# Atom_S3_Module_-_Rev_C.net
KiCad netlist of a schematic drawn in EAGLE
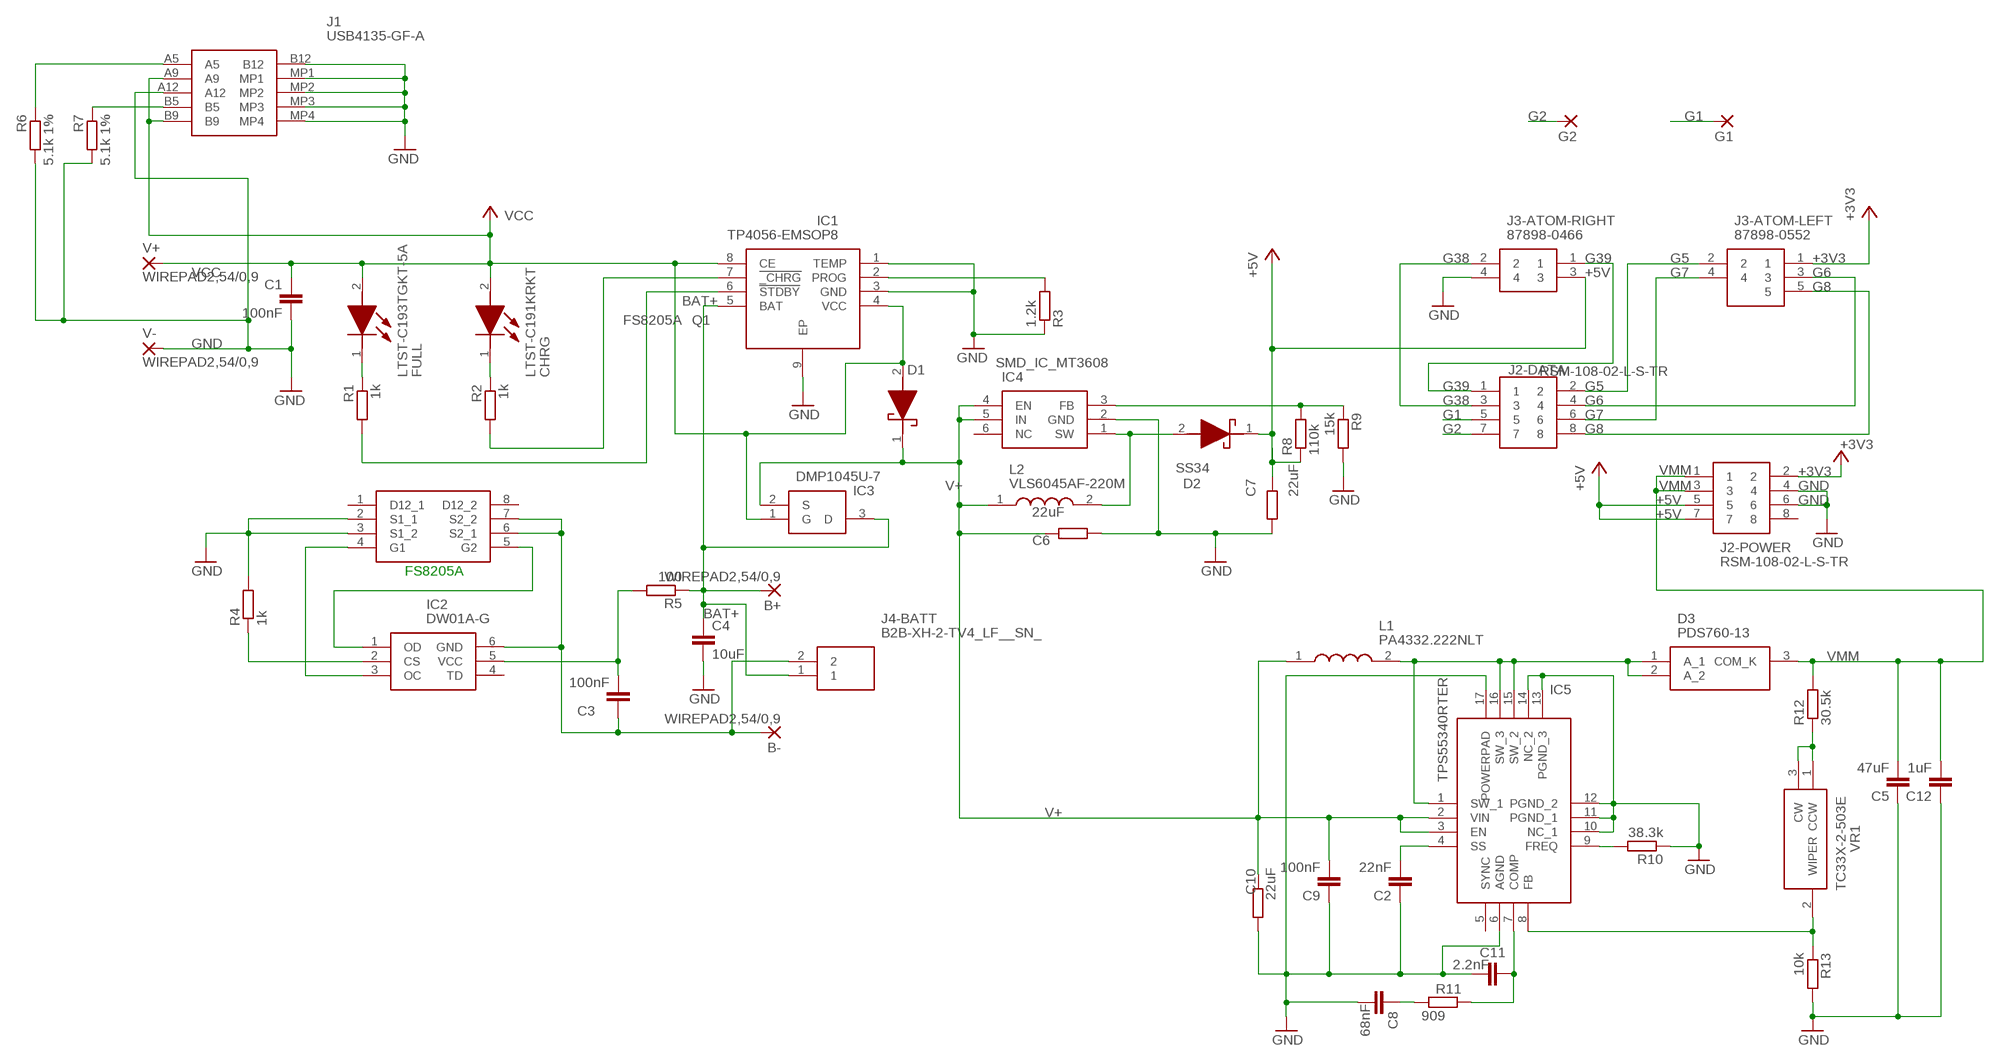
[diagram p0: schematic, sheet 1]

(export (version "E")
  (design (tool "Eeschema 10.0.6"))
  (components
    (comp (ref "B+")
      (value "WIREPAD2,54/0,9")
      (footprint "eagle-import:2,54_0,9")
      (libsource (lib "eagle-import") (part "WIREPAD2,54/0,9"))
    )
    (comp (ref "B-")
      (value "WIREPAD2,54/0,9")
      (footprint "eagle-import:2,54_0,9")
      (libsource (lib "eagle-import") (part "WIREPAD2,54/0,9"))
    )
    (comp (ref "C1")
      (value "100nF")
      (footprint "eagle-import:C0603")
      (libsource (lib "eagle-import") (part "C-EUC0603"))
    )
    (comp (ref "C2")
      (value "22nF")
      (footprint "eagle-import:C0603")
      (libsource (lib "eagle-import") (part "C-EUC0603"))
    )
    (comp (ref "C3")
      (value "100nF")
      (footprint "eagle-import:C0603")
      (libsource (lib "eagle-import") (part "C-EUC0603"))
    )
    (comp (ref "C4")
      (value "10uF")
      (footprint "eagle-import:C0603")
      (libsource (lib "eagle-import") (part "C-EUC0603"))
    )
    (comp (ref "C5")
      (value "47uF")
      (footprint "eagle-import:C1210")
      (libsource (lib "eagle-import") (part "C-EUC1210"))
    )
    (comp (ref "C6")
      (value "22uF")
      (footprint "eagle-import:R0805")
      (libsource (lib "eagle-import") (part "R-EU_R0805"))
    )
    (comp (ref "C7")
      (value "22uF")
      (footprint "eagle-import:R0805")
      (libsource (lib "eagle-import") (part "R-EU_R0805"))
    )
    (comp (ref "C8")
      (value "68nF")
      (footprint "eagle-import:C0603")
      (libsource (lib "eagle-import") (part "C-EUC0603"))
    )
    (comp (ref "C9")
      (value "100nF")
      (footprint "eagle-import:C0603")
      (libsource (lib "eagle-import") (part "C-EUC0603"))
    )
    (comp (ref "C10")
      (value "22uF")
      (footprint "eagle-import:R0805")
      (libsource (lib "eagle-import") (part "R-EU_R0805"))
    )
    (comp (ref "C11")
      (value "2.2nF")
      (footprint "eagle-import:C0603")
      (libsource (lib "eagle-import") (part "C-EUC0603"))
    )
    (comp (ref "C12")
      (value "1uF")
      (footprint "eagle-import:C0603")
      (libsource (lib "eagle-import") (part "C-EUC0603"))
    )
    (comp (ref "CHRG")
      (value "LTST-C191KRKT")
      (footprint "eagle-import:LEDC1608X55N")
      (fields (field (name "MOUSER_PART_NUMBER") "859-LTST-C191KRKT"))
      (libsource (lib "eagle-import") (part "LTST-C191KRKT"))
    )
    (comp (ref "D1")
      (value "SS34")
      (footprint "eagle-import:DIOM8059X256N")
      (fields (field (name "MOUSER_PART_NUMBER") "512-SS34"))
      (libsource (lib "eagle-import") (part "SS34"))
    )
    (comp (ref "D2")
      (value "SS34")
      (footprint "eagle-import:DIOM8059X256N")
      (fields (field (name "MOUSER_PART_NUMBER") "512-SS34"))
      (libsource (lib "eagle-import") (part "SS34"))
    )
    (comp (ref "D3")
      (value "PDS760-13")
      (footprint "eagle-import:PDS76013")
      (fields (field (name "MOUSER_PART_NUMBER") "621-PDS760-F"))
      (libsource (lib "eagle-import") (part "PDS760-13"))
    )
    (comp (ref "FULL")
      (value "LTST-C193TGKT-5A")
      (footprint "eagle-import:LEDC1608X45N")
      (fields (field (name "MOUSER_PART_NUMBER") "859-LTSTC193TGKT5A"))
      (libsource (lib "eagle-import") (part "LTST-C193TGKT-5A"))
    )
    (comp (ref "G1")
      (value "WIREPAD1,6/0,9")
      (footprint "eagle-import:1,6_0,9")
      (libsource (lib "eagle-import") (part "WIREPAD1,6/0,9"))
    )
    (comp (ref "G2")
      (value "WIREPAD1,6/0,9")
      (footprint "eagle-import:1,6_0,9")
      (libsource (lib "eagle-import") (part "WIREPAD1,6/0,9"))
    )
    (comp (ref "IC1")
      (value "TP4056-EMSOP8")
      (footprint "eagle-import:SOP65P490X110-9N")
      (libsource (lib "eagle-import") (part "TP4056-EMSOP8"))
    )
    (comp (ref "IC2")
      (value "DW01A-G")
      (footprint "eagle-import:SOT95P190X145-6N")
      (libsource (lib "eagle-import") (part "DW01A-G"))
    )
    (comp (ref "IC3")
      (value "DMP1045U-7")
      (footprint "eagle-import:SOT96P240X110-3N")
      (fields (field (name "MOUSER_PART_NUMBER") "621-DMP1045U-7"))
      (libsource (lib "eagle-import") (part "DMP1045U-7"))
    )
    (comp (ref "IC4")
      (value "SMD_IC_MT3608")
      (footprint "eagle-import:SOT95P280X145-6N")
      (fields
        (field (name "MANUFACTURER_PART_NUMBER") "SMD IC MT3608")
        (field (name "MOUSER_PART_NUMBER") "909-SMDICMT3608")
      )
      (libsource (lib "eagle-import") (part "SMD_IC_MT3608"))
    )
    (comp (ref "IC5")
      (value "TPS55340RTER")
      (footprint "eagle-import:QFN50P300X300X80-17N")
      (fields (field (name "MOUSER_PART_NUMBER") "595-TPS55340RTER"))
      (libsource (lib "eagle-import") (part "TPS55340RTER"))
    )
    (comp (ref "J1")
      (value "USB4135-GF-A")
      (footprint "eagle-import:USB4135GFA")
      (fields (field (name "MOUSER_PART_NUMBER") "640-USB4135-GF-A"))
      (libsource (lib "eagle-import") (part "USB4135-GF-A"))
    )
    (comp (ref "J2-DATA")
      (value "RSM-108-02-L-S-TR")
      (footprint "eagle-import:RSM10802LSTR")
      (fields (field (name "MOUSER_PART_NUMBER") "200-RSM10802LSTR"))
      (libsource (lib "eagle-import") (part "RSM-108-02-L-S-TR"))
    )
    (comp (ref "J2-POWER")
      (value "RSM-108-02-L-S-TR")
      (footprint "eagle-import:RSM10802LSTR")
      (fields (field (name "MOUSER_PART_NUMBER") "200-RSM10802LSTR"))
      (libsource (lib "eagle-import") (part "RSM-108-02-L-S-TR"))
    )
    (comp (ref "J3-ATOM-LEFT")
      (value "87898-0552")
      (footprint "eagle-import:878980552")
      (libsource (lib "eagle-import") (part "87898-0552"))
    )
    (comp (ref "J3-ATOM-RIGHT")
      (value "87898-0466")
      (footprint "eagle-import:878980466")
      (fields (field (name "MOUSER_PART_NUMBER") "538-87898-0466"))
      (libsource (lib "eagle-import") (part "87898-0466"))
    )
    (comp (ref "J4-BATT")
      (value "B2B-XH-2-TV4_LF__SN_")
      (footprint "eagle-import:B2BXH2TV4LFSN")
      (fields
        (field (name "MANUFACTURER_PART_NUMBER") "B2B-XH-2-TV4(LF)(SN)")
        (field (name "MOUSER_PART_NUMBER") "306-B2BXH2TV4LFSN")
      )
      (libsource (lib "eagle-import") (part "B2B-XH-2-TV4_LF__SN_"))
    )
    (comp (ref "L1")
      (value "PA4332.222NLT")
      (footprint "eagle-import:INDPM4042X200N")
      (fields (field (name "MOUSER_PART_NUMBER") "673-PA4332222NLT"))
      (libsource (lib "eagle-import") (part "PA4332.222NLT"))
    )
    (comp (ref "L2")
      (value "VLS6045AF-220M")
      (footprint "eagle-import:VLS6045")
      (fields (field (name "MOUSER_PART_NUMBER") "810-VLS6045AF-220M"))
      (libsource (lib "eagle-import") (part "VLS6045AF-220M"))
    )
    (comp (ref "Q1")
      (value "FS8205A")
      (footprint "eagle-import:SOP65P640X120-8N")
      (libsource (lib "eagle-import") (part "FS8205A"))
    )
    (comp (ref "R1")
      (value "1k")
      (footprint "eagle-import:R0603")
      (libsource (lib "eagle-import") (part "R-EU_R0603"))
    )
    (comp (ref "R2")
      (value "1k")
      (footprint "eagle-import:R0603")
      (libsource (lib "eagle-import") (part "R-EU_R0603"))
    )
    (comp (ref "R3")
      (value "1.2k")
      (footprint "eagle-import:R0603")
      (libsource (lib "eagle-import") (part "R-EU_R0603"))
    )
    (comp (ref "R4")
      (value "1k")
      (footprint "eagle-import:R0603")
      (libsource (lib "eagle-import") (part "R-EU_R0603"))
    )
    (comp (ref "R5")
      (value "100")
      (footprint "eagle-import:R0603")
      (libsource (lib "eagle-import") (part "R-EU_R0603"))
    )
    (comp (ref "R6")
      (value "5.1k 1%")
      (footprint "eagle-import:R0603")
      (libsource (lib "eagle-import") (part "R-EU_R0603"))
    )
    (comp (ref "R7")
      (value "5.1k 1%")
      (footprint "eagle-import:R0603")
      (libsource (lib "eagle-import") (part "R-EU_R0603"))
    )
    (comp (ref "R8")
      (value "110k")
      (footprint "eagle-import:R0603")
      (libsource (lib "eagle-import") (part "R-EU_R0603"))
    )
    (comp (ref "R9")
      (value "15k")
      (footprint "eagle-import:R0603")
      (libsource (lib "eagle-import") (part "R-EU_R0603"))
    )
    (comp (ref "R10")
      (value "38.3k")
      (footprint "eagle-import:R0603")
      (libsource (lib "eagle-import") (part "R-EU_R0603"))
    )
    (comp (ref "R11")
      (value "909")
      (footprint "eagle-import:R0603")
      (libsource (lib "eagle-import") (part "R-EU_R0603"))
    )
    (comp (ref "R12")
      (value "30.5k")
      (footprint "eagle-import:R0805")
      (libsource (lib "eagle-import") (part "R-EU_R0805"))
    )
    (comp (ref "R13")
      (value "10k")
      (footprint "eagle-import:R0603")
      (libsource (lib "eagle-import") (part "R-EU_R0603"))
    )
    (comp (ref "V+")
      (value "WIREPAD2,54/0,9")
      (footprint "eagle-import:2,54_0,9")
      (libsource (lib "eagle-import") (part "WIREPAD2,54/0,9"))
    )
    (comp (ref "V-")
      (value "WIREPAD2,54/0,9")
      (footprint "eagle-import:2,54_0,9")
      (libsource (lib "eagle-import") (part "WIREPAD2,54/0,9"))
    )
    (comp (ref "VR1")
      (value "TC33X-2-503E")
      (footprint "eagle-import:TC33X2503E")
      (fields (field (name "MOUSER_PART_NUMBER") "652-TC33X-2-503E"))
      (libsource (lib "eagle-import") (part "TC33X-2-503E"))
    )
  )
  (nets
    (net (code "1") (name "+3V3") (class "Default")
      (node (ref "J2-POWER") (pin "2") (pinfunction "2_2") (pintype "bidirectional"))
      (node (ref "J3-ATOM-LEFT") (pin "1") (pinfunction "1_1") (pintype "bidirectional"))
    )
    (net (code "2") (name "+5V") (class "Default")
      (node (ref "C7") (pin "2") (pinfunction "2_2") (pintype "passive"))
      (node (ref "D2") (pin "1") (pinfunction "K_1") (pintype "bidirectional"))
      (node (ref "J2-POWER") (pin "5") (pinfunction "5_5") (pintype "bidirectional"))
      (node (ref "J2-POWER") (pin "7") (pinfunction "7_7") (pintype "bidirectional"))
      (node (ref "J3-ATOM-RIGHT") (pin "3") (pinfunction "3_3") (pintype "bidirectional"))
      (node (ref "R8") (pin "1") (pinfunction "1_1") (pintype "passive"))
    )
    (net (code "3") (name "BAT+") (class "Default")
      (node (ref "B+") (pin "1") (pinfunction "P_1") (pintype "passive"))
      (node (ref "C4") (pin "1") (pinfunction "1_1") (pintype "passive"))
      (node (ref "IC1") (pin "5") (pinfunction "BAT_5") (pintype "bidirectional"))
      (node (ref "IC3") (pin "3") (pinfunction "D_3") (pintype "bidirectional"))
      (node (ref "J4-BATT") (pin "1") (pinfunction "1_1") (pintype "bidirectional"))
      (node (ref "R5") (pin "1") (pinfunction "1_1") (pintype "passive"))
    )
    (net (code "4") (name "G1") (class "Default")
      (node (ref "G1") (pin "1") (pinfunction "P_1") (pintype "passive"))
      (node (ref "J2-DATA") (pin "5") (pinfunction "5_5") (pintype "bidirectional"))
    )
    (net (code "5") (name "G2") (class "Default")
      (node (ref "G2") (pin "1") (pinfunction "P_1") (pintype "passive"))
      (node (ref "J2-DATA") (pin "7") (pinfunction "7_7") (pintype "bidirectional"))
    )
    (net (code "6") (name "G5") (class "Default")
      (node (ref "J2-DATA") (pin "2") (pinfunction "2_2") (pintype "bidirectional"))
      (node (ref "J3-ATOM-LEFT") (pin "2") (pinfunction "2_2") (pintype "bidirectional"))
    )
    (net (code "7") (name "G6") (class "Default")
      (node (ref "J2-DATA") (pin "4") (pinfunction "4_4") (pintype "bidirectional"))
      (node (ref "J3-ATOM-LEFT") (pin "3") (pinfunction "3_3") (pintype "bidirectional"))
    )
    (net (code "8") (name "G7") (class "Default")
      (node (ref "J2-DATA") (pin "6") (pinfunction "6_6") (pintype "bidirectional"))
      (node (ref "J3-ATOM-LEFT") (pin "4") (pinfunction "4_4") (pintype "bidirectional"))
    )
    (net (code "9") (name "G8") (class "Default")
      (node (ref "J2-DATA") (pin "8") (pinfunction "8_8") (pintype "bidirectional"))
      (node (ref "J3-ATOM-LEFT") (pin "5") (pinfunction "5_5") (pintype "bidirectional"))
    )
    (net (code "10") (name "G38") (class "Default")
      (node (ref "J2-DATA") (pin "3") (pinfunction "3_3") (pintype "bidirectional"))
      (node (ref "J3-ATOM-RIGHT") (pin "2") (pinfunction "2_2") (pintype "bidirectional"))
    )
    (net (code "11") (name "G39") (class "Default")
      (node (ref "J2-DATA") (pin "1") (pinfunction "1_1") (pintype "bidirectional"))
      (node (ref "J3-ATOM-RIGHT") (pin "1") (pinfunction "1_1") (pintype "bidirectional"))
    )
    (net (code "12") (name "GND") (class "Default")
      (node (ref "C1") (pin "2") (pinfunction "2_2") (pintype "passive"))
      (node (ref "C10") (pin "1") (pinfunction "1_1") (pintype "passive"))
      (node (ref "C11") (pin "2") (pinfunction "2_2") (pintype "passive"))
      (node (ref "C12") (pin "1") (pinfunction "1_1") (pintype "passive"))
      (node (ref "C2") (pin "1") (pinfunction "1_1") (pintype "passive"))
      (node (ref "C4") (pin "2") (pinfunction "2_2") (pintype "passive"))
      (node (ref "C5") (pin "1") (pinfunction "1_1") (pintype "passive"))
      (node (ref "C6") (pin "1") (pinfunction "1_1") (pintype "passive"))
      (node (ref "C7") (pin "1") (pinfunction "1_1") (pintype "passive"))
      (node (ref "C8") (pin "2") (pinfunction "2_2") (pintype "passive"))
      (node (ref "C9") (pin "1") (pinfunction "1_1") (pintype "passive"))
      (node (ref "IC1") (pin "1") (pinfunction "TEMP_1") (pintype "bidirectional"))
      (node (ref "IC1") (pin "3") (pinfunction "GND_3") (pintype "bidirectional"))
      (node (ref "IC1") (pin "9") (pinfunction "EP_9") (pintype "bidirectional"))
      (node (ref "IC4") (pin "2") (pinfunction "GND_2") (pintype "bidirectional"))
      (node (ref "IC5") (pin "10") (pinfunction "NC_1_10") (pintype "bidirectional"))
      (node (ref "IC5") (pin "11") (pinfunction "PGND_1_11") (pintype "bidirectional"))
      (node (ref "IC5") (pin "12") (pinfunction "PGND_2_12") (pintype "bidirectional"))
      (node (ref "IC5") (pin "13") (pinfunction "PGND_3_13") (pintype "bidirectional"))
      (node (ref "IC5") (pin "14") (pinfunction "NC_2_14") (pintype "bidirectional"))
      (node (ref "IC5") (pin "17") (pinfunction "POWERPAD_17") (pintype "bidirectional"))
      (node (ref "IC5") (pin "6") (pinfunction "AGND_6") (pintype "bidirectional"))
      (node (ref "J1") (pin "A12") (pinfunction "A12_A12") (pintype "bidirectional"))
      (node (ref "J1") (pin "B12") (pinfunction "B12_B12") (pintype "bidirectional"))
      (node (ref "J1") (pin "MP1") (pinfunction "MP1_MP1") (pintype "bidirectional"))
      (node (ref "J1") (pin "MP2") (pinfunction "MP2_MP2") (pintype "bidirectional"))
      (node (ref "J1") (pin "MP3") (pinfunction "MP3_MP3") (pintype "bidirectional"))
      (node (ref "J1") (pin "MP4") (pinfunction "MP4_MP4") (pintype "bidirectional"))
      (node (ref "J2-POWER") (pin "4") (pinfunction "4_4") (pintype "bidirectional"))
      (node (ref "J2-POWER") (pin "6") (pinfunction "6_6") (pintype "bidirectional"))
      (node (ref "J3-ATOM-RIGHT") (pin "4") (pinfunction "4_4") (pintype "bidirectional"))
      (node (ref "Q1") (pin "2") (pinfunction "S1_1_2") (pintype "bidirectional"))
      (node (ref "Q1") (pin "3") (pinfunction "S1_2_3") (pintype "bidirectional"))
      (node (ref "R10") (pin "1") (pinfunction "1_1") (pintype "passive"))
      (node (ref "R13") (pin "2") (pinfunction "2_2") (pintype "passive"))
      (node (ref "R3") (pin "1") (pinfunction "1_1") (pintype "passive"))
      (node (ref "R4") (pin "2") (pinfunction "2_2") (pintype "passive"))
      (node (ref "R6") (pin "2") (pinfunction "2_2") (pintype "passive"))
      (node (ref "R7") (pin "2") (pinfunction "2_2") (pintype "passive"))
      (node (ref "R9") (pin "2") (pinfunction "2_2") (pintype "passive"))
      (node (ref "V-") (pin "1") (pinfunction "P_1") (pintype "passive"))
    )
    (net (code "13") (name "Net-(B--P)") (class "Default")
      (node (ref "B-") (pin "1") (pinfunction "P_1") (pintype "passive"))
      (node (ref "C3") (pin "1") (pinfunction "1_1") (pintype "passive"))
      (node (ref "IC2") (pin "6") (pinfunction "GND_6") (pintype "bidirectional"))
      (node (ref "J4-BATT") (pin "2") (pinfunction "2_2") (pintype "bidirectional"))
      (node (ref "Q1") (pin "6") (pinfunction "S2_1_6") (pintype "bidirectional"))
      (node (ref "Q1") (pin "7") (pinfunction "S2_2_7") (pintype "bidirectional"))
    )
    (net (code "14") (name "Net-(C8-Pad1)") (class "Default")
      (node (ref "C8") (pin "1") (pinfunction "1_1") (pintype "passive"))
      (node (ref "R11") (pin "1") (pinfunction "1_1") (pintype "passive"))
    )
    (net (code "15") (name "Net-(CHRG-K)") (class "Default")
      (node (ref "CHRG") (pin "1") (pinfunction "K_1") (pintype "bidirectional"))
      (node (ref "R2") (pin "1") (pinfunction "1_1") (pintype "passive"))
    )
    (net (code "16") (name "Net-(D2-A)") (class "Default")
      (node (ref "D2") (pin "2") (pinfunction "A_2") (pintype "bidirectional"))
      (node (ref "IC4") (pin "1") (pinfunction "SW_1") (pintype "bidirectional"))
      (node (ref "L2") (pin "2") (pinfunction "2_2") (pintype "bidirectional"))
    )
    (net (code "17") (name "Net-(D3-A_1)") (class "Default")
      (node (ref "D3") (pin "1") (pinfunction "A_1_1") (pintype "bidirectional"))
      (node (ref "D3") (pin "2") (pinfunction "A_2_2") (pintype "bidirectional"))
      (node (ref "IC5") (pin "1") (pinfunction "SW_1_1") (pintype "bidirectional"))
      (node (ref "IC5") (pin "15") (pinfunction "SW_2_15") (pintype "bidirectional"))
      (node (ref "IC5") (pin "16") (pinfunction "SW_3_16") (pintype "bidirectional"))
      (node (ref "L1") (pin "2") (pinfunction "2_2") (pintype "bidirectional"))
    )
    (net (code "18") (name "Net-(FULL-K)") (class "Default")
      (node (ref "FULL") (pin "1") (pinfunction "K_1") (pintype "bidirectional"))
      (node (ref "R1") (pin "1") (pinfunction "1_1") (pintype "passive"))
    )
    (net (code "19") (name "Net-(IC1-PROG)") (class "Default")
      (node (ref "IC1") (pin "2") (pinfunction "PROG_2") (pintype "bidirectional"))
      (node (ref "R3") (pin "2") (pinfunction "2_2") (pintype "passive"))
    )
    (net (code "20") (name "Net-(IC1-~{STDBY})") (class "Default")
      (node (ref "IC1") (pin "6") (pinfunction "~{STDBY}_6") (pintype "bidirectional"))
      (node (ref "R1") (pin "2") (pinfunction "2_2") (pintype "passive"))
    )
    (net (code "21") (name "Net-(IC1-~{_CHRG})") (class "Default")
      (node (ref "IC1") (pin "7") (pinfunction "~{_CHRG}_7") (pintype "bidirectional"))
      (node (ref "R2") (pin "2") (pinfunction "2_2") (pintype "passive"))
    )
    (net (code "22") (name "Net-(IC2-CS)") (class "Default")
      (node (ref "IC2") (pin "2") (pinfunction "CS_2") (pintype "bidirectional"))
      (node (ref "R4") (pin "1") (pinfunction "1_1") (pintype "passive"))
    )
    (net (code "23") (name "Net-(IC2-OC)") (class "Default")
      (node (ref "IC2") (pin "3") (pinfunction "OC_3") (pintype "bidirectional"))
      (node (ref "Q1") (pin "4") (pinfunction "G1_4") (pintype "bidirectional"))
    )
    (net (code "24") (name "Net-(IC2-OD)") (class "Default")
      (node (ref "IC2") (pin "1") (pinfunction "OD_1") (pintype "bidirectional"))
      (node (ref "Q1") (pin "5") (pinfunction "G2_5") (pintype "bidirectional"))
    )
    (net (code "25") (name "Net-(IC2-VCC)") (class "Default")
      (node (ref "C3") (pin "2") (pinfunction "2_2") (pintype "passive"))
      (node (ref "IC2") (pin "5") (pinfunction "VCC_5") (pintype "bidirectional"))
      (node (ref "R5") (pin "2") (pinfunction "2_2") (pintype "passive"))
    )
    (net (code "26") (name "Net-(IC4-FB)") (class "Default")
      (node (ref "IC4") (pin "3") (pinfunction "FB_3") (pintype "bidirectional"))
      (node (ref "R8") (pin "2") (pinfunction "2_2") (pintype "passive"))
      (node (ref "R9") (pin "1") (pinfunction "1_1") (pintype "passive"))
    )
    (net (code "27") (name "Net-(IC5-COMP)") (class "Default")
      (node (ref "C11") (pin "1") (pinfunction "1_1") (pintype "passive"))
      (node (ref "IC5") (pin "7") (pinfunction "COMP_7") (pintype "bidirectional"))
      (node (ref "R11") (pin "2") (pinfunction "2_2") (pintype "passive"))
    )
    (net (code "28") (name "Net-(IC5-FB)") (class "Default")
      (node (ref "IC5") (pin "8") (pinfunction "FB_8") (pintype "bidirectional"))
      (node (ref "R13") (pin "1") (pinfunction "1_1") (pintype "passive"))
      (node (ref "VR1") (pin "2") (pinfunction "WIPER_2") (pintype "bidirectional"))
    )
    (net (code "29") (name "Net-(IC5-FREQ)") (class "Default")
      (node (ref "IC5") (pin "9") (pinfunction "FREQ_9") (pintype "bidirectional"))
      (node (ref "R10") (pin "2") (pinfunction "2_2") (pintype "passive"))
    )
    (net (code "30") (name "Net-(IC5-SS)") (class "Default")
      (node (ref "C2") (pin "2") (pinfunction "2_2") (pintype "passive"))
      (node (ref "IC5") (pin "4") (pinfunction "SS_4") (pintype "bidirectional"))
    )
    (net (code "31") (name "Net-(J1-PadA5)") (class "Default")
      (node (ref "J1") (pin "A5") (pinfunction "A5_A5") (pintype "bidirectional"))
      (node (ref "R6") (pin "1") (pinfunction "1_1") (pintype "passive"))
    )
    (net (code "32") (name "Net-(J1-PadB5)") (class "Default")
      (node (ref "J1") (pin "B5") (pinfunction "B5_B5") (pintype "bidirectional"))
      (node (ref "R7") (pin "1") (pinfunction "1_1") (pintype "passive"))
    )
    (net (code "33") (name "Net-(VR1-CCW)") (class "Default")
      (node (ref "R12") (pin "1") (pinfunction "1_1") (pintype "passive"))
      (node (ref "VR1") (pin "1") (pinfunction "CCW_1") (pintype "bidirectional"))
      (node (ref "VR1") (pin "3") (pinfunction "CW_3") (pintype "bidirectional"))
    )
    (net (code "34") (name "V+") (class "Default")
      (node (ref "C10") (pin "2") (pinfunction "2_2") (pintype "passive"))
      (node (ref "C6") (pin "2") (pinfunction "2_2") (pintype "passive"))
      (node (ref "C9") (pin "2") (pinfunction "2_2") (pintype "passive"))
      (node (ref "D1") (pin "1") (pinfunction "K_1") (pintype "bidirectional"))
      (node (ref "IC3") (pin "2") (pinfunction "S_2") (pintype "bidirectional"))
      (node (ref "IC4") (pin "4") (pinfunction "EN_4") (pintype "bidirectional"))
      (node (ref "IC4") (pin "5") (pinfunction "IN_5") (pintype "bidirectional"))
      (node (ref "IC5") (pin "2") (pinfunction "VIN_2") (pintype "bidirectional"))
      (node (ref "IC5") (pin "3") (pinfunction "EN_3") (pintype "bidirectional"))
      (node (ref "L1") (pin "1") (pinfunction "1_1") (pintype "bidirectional"))
      (node (ref "L2") (pin "1") (pinfunction "1_1") (pintype "bidirectional"))
    )
    (net (code "35") (name "VCC") (class "Default")
      (node (ref "C1") (pin "1") (pinfunction "1_1") (pintype "passive"))
      (node (ref "CHRG") (pin "2") (pinfunction "A_2") (pintype "bidirectional"))
      (node (ref "D1") (pin "2") (pinfunction "A_2") (pintype "bidirectional"))
      (node (ref "FULL") (pin "2") (pinfunction "A_2") (pintype "bidirectional"))
      (node (ref "IC1") (pin "4") (pinfunction "VCC_4") (pintype "bidirectional"))
      (node (ref "IC1") (pin "8") (pinfunction "CE_8") (pintype "bidirectional"))
      (node (ref "IC3") (pin "1") (pinfunction "G_1") (pintype "bidirectional"))
      (node (ref "J1") (pin "A9") (pinfunction "A9_A9") (pintype "bidirectional"))
      (node (ref "J1") (pin "B9") (pinfunction "B9_B9") (pintype "bidirectional"))
      (node (ref "V+") (pin "1") (pinfunction "P_1") (pintype "passive"))
    )
    (net (code "36") (name "VMM") (class "Default")
      (node (ref "C12") (pin "2") (pinfunction "2_2") (pintype "passive"))
      (node (ref "C5") (pin "2") (pinfunction "2_2") (pintype "passive"))
      (node (ref "D3") (pin "3") (pinfunction "COM_K_3") (pintype "bidirectional"))
      (node (ref "J2-POWER") (pin "1") (pinfunction "1_1") (pintype "bidirectional"))
      (node (ref "J2-POWER") (pin "3") (pinfunction "3_3") (pintype "bidirectional"))
      (node (ref "R12") (pin "2") (pinfunction "2_2") (pintype "passive"))
    )
    (net (code "37") (name "unconnected-(IC2-TD-Pad4)") (class "Default")
      (node (ref "IC2") (pin "4") (pinfunction "TD_4") (pintype "bidirectional"))
    )
    (net (code "38") (name "unconnected-(IC4-NC-Pad6)") (class "Default")
      (node (ref "IC4") (pin "6") (pinfunction "NC_6") (pintype "no_connect"))
    )
    (net (code "39") (name "unconnected-(IC5-SYNC-Pad5)") (class "Default")
      (node (ref "IC5") (pin "5") (pinfunction "SYNC_5") (pintype "bidirectional"))
    )
    (net (code "40") (name "unconnected-(J2-POWER-Pad8)") (class "Default")
      (node (ref "J2-POWER") (pin "8") (pinfunction "8_8") (pintype "bidirectional"))
    )
    (net (code "41") (name "unconnected-(Q1-D12_1-Pad1)") (class "Default")
      (node (ref "Q1") (pin "1") (pinfunction "D12_1_1") (pintype "bidirectional"))
    )
    (net (code "42") (name "unconnected-(Q1-D12_2-Pad8)") (class "Default")
      (node (ref "Q1") (pin "8") (pinfunction "D12_2_8") (pintype "bidirectional"))
    )
  )
)
